# digit_8.net
KiCad netlist of a schematic drawn in EAGLE
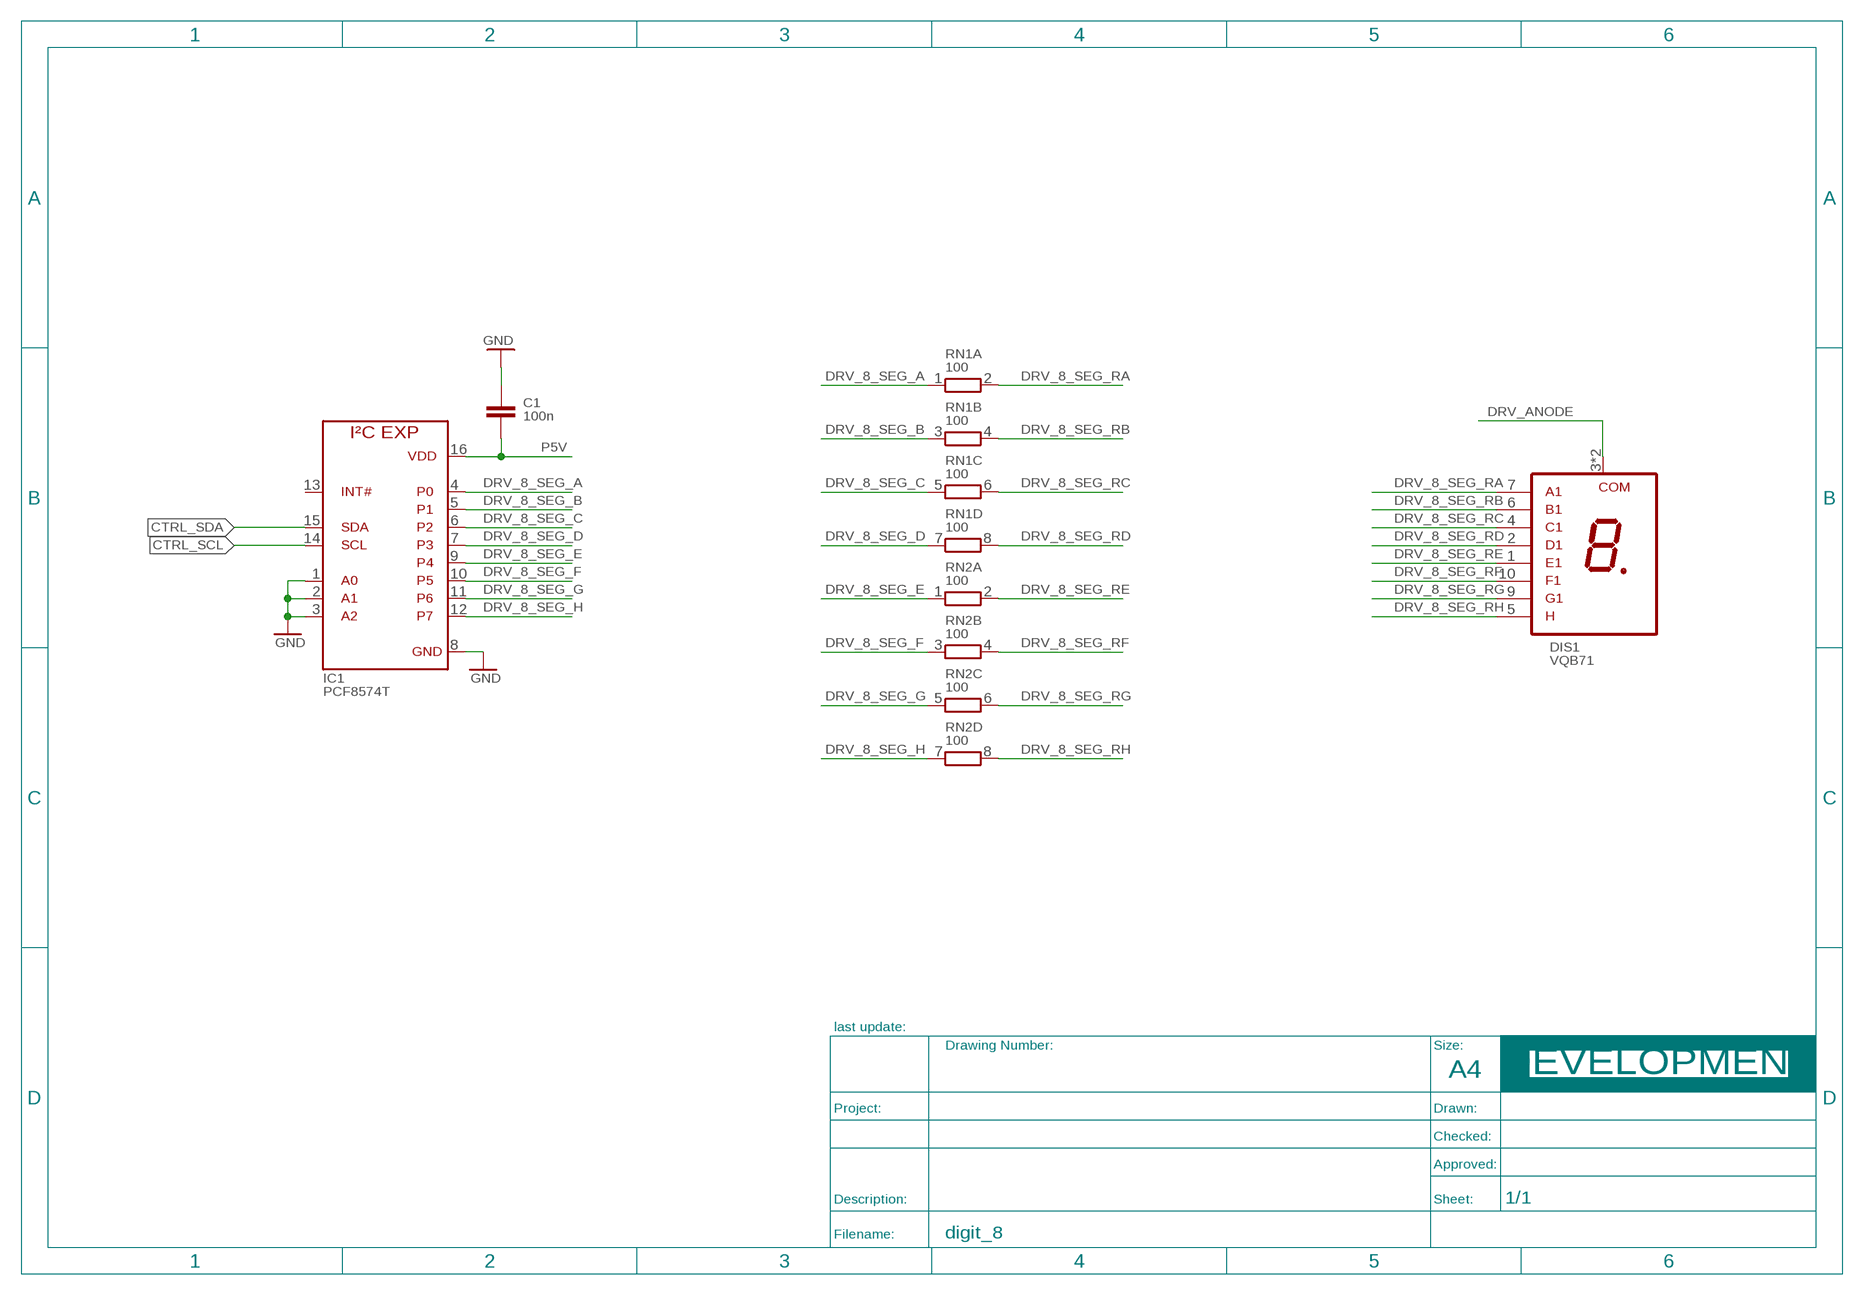
[diagram p0: schematic, sheet 1]

(export (version "E")
  (design (tool "Eeschema 10.0.6"))
  (components
    (comp (ref "C1")
      (value "100n")
      (footprint "eagle-import:S_0805")
      (fields (field (name "PART_CODE_BEL") "C_PAC_S_0805_VAL_100n"))
      (libsource (lib "eagle-import") (part "C_EU_S_0805"))
    )
    (comp (ref "DIS1")
      (value "VQB71")
      (footprint "eagle-import:T_VQB71")
      (libsource (lib "eagle-import") (part "VQB71"))
    )
    (comp (ref "IC1")
      (value "PCF8574T")
      (footprint "eagle-import:S_SOIC16")
      (libsource (lib "eagle-import") (part "PCF8574T"))
    )
    (comp (ref "RN1")
      (value "100")
      (footprint "eagle-import:T_SIL8")
      (fields (field (name "PART_CODE_BEL") "RN_PAC_T_SIL8_VAL_100"))
      (libsource (lib "eagle-import") (part "R_EU_ARRAY_4"))
    )
    (comp (ref "RN2")
      (value "100")
      (footprint "eagle-import:T_SIL8")
      (fields (field (name "PART_CODE_BEL") "RN_PAC_T_SIL8_VAL_100"))
      (libsource (lib "eagle-import") (part "R_EU_ARRAY_4"))
    )
  )
  (nets
    (net (code "1") (name "/DRV_8_SEG_A") (class "Default")
      (node (ref "IC1") (pin "4") (pinfunction "P0_4") (pintype "bidirectional"))
      (node (ref "RN1") (pin "1") (pinfunction "1_1") (pintype "passive"))
    )
    (net (code "2") (name "/DRV_8_SEG_B") (class "Default")
      (node (ref "IC1") (pin "5") (pinfunction "P1_5") (pintype "bidirectional"))
      (node (ref "RN1") (pin "3") (pinfunction "1_3") (pintype "passive"))
    )
    (net (code "3") (name "/DRV_8_SEG_C") (class "Default")
      (node (ref "IC1") (pin "6") (pinfunction "P2_6") (pintype "bidirectional"))
      (node (ref "RN1") (pin "5") (pinfunction "1_5") (pintype "passive"))
    )
    (net (code "4") (name "/DRV_8_SEG_D") (class "Default")
      (node (ref "IC1") (pin "7") (pinfunction "P3_7") (pintype "bidirectional"))
      (node (ref "RN1") (pin "7") (pinfunction "1_7") (pintype "passive"))
    )
    (net (code "5") (name "/DRV_8_SEG_E") (class "Default")
      (node (ref "IC1") (pin "9") (pinfunction "P4_9") (pintype "bidirectional"))
      (node (ref "RN2") (pin "1") (pinfunction "1_1") (pintype "passive"))
    )
    (net (code "6") (name "/DRV_8_SEG_F") (class "Default")
      (node (ref "IC1") (pin "10") (pinfunction "P5_10") (pintype "bidirectional"))
      (node (ref "RN2") (pin "3") (pinfunction "1_3") (pintype "passive"))
    )
    (net (code "7") (name "/DRV_8_SEG_G") (class "Default")
      (node (ref "IC1") (pin "11") (pinfunction "P6_11") (pintype "bidirectional"))
      (node (ref "RN2") (pin "5") (pinfunction "1_5") (pintype "passive"))
    )
    (net (code "8") (name "/DRV_8_SEG_H") (class "Default")
      (node (ref "IC1") (pin "12") (pinfunction "P7_12") (pintype "bidirectional"))
      (node (ref "RN2") (pin "7") (pinfunction "1_7") (pintype "passive"))
    )
    (net (code "9") (name "/DRV_8_SEG_RA") (class "Default")
      (node (ref "DIS1") (pin "7") (pinfunction "A1_7") (pintype "passive"))
      (node (ref "RN1") (pin "2") (pinfunction "2_2") (pintype "passive"))
    )
    (net (code "10") (name "/DRV_8_SEG_RB") (class "Default")
      (node (ref "DIS1") (pin "6") (pinfunction "B1_6") (pintype "passive"))
      (node (ref "RN1") (pin "4") (pinfunction "2_4") (pintype "passive"))
    )
    (net (code "11") (name "/DRV_8_SEG_RC") (class "Default")
      (node (ref "DIS1") (pin "4") (pinfunction "C1_4") (pintype "passive"))
      (node (ref "RN1") (pin "6") (pinfunction "2_6") (pintype "passive"))
    )
    (net (code "12") (name "/DRV_8_SEG_RD") (class "Default")
      (node (ref "DIS1") (pin "2") (pinfunction "D1_2") (pintype "passive"))
      (node (ref "RN1") (pin "8") (pinfunction "2_8") (pintype "passive"))
    )
    (net (code "13") (name "/DRV_8_SEG_RE") (class "Default")
      (node (ref "DIS1") (pin "1") (pinfunction "E1_1") (pintype "passive"))
      (node (ref "RN2") (pin "2") (pinfunction "2_2") (pintype "passive"))
    )
    (net (code "14") (name "/DRV_8_SEG_RF") (class "Default")
      (node (ref "DIS1") (pin "10") (pinfunction "F1_10") (pintype "passive"))
      (node (ref "RN2") (pin "4") (pinfunction "2_4") (pintype "passive"))
    )
    (net (code "15") (name "/DRV_8_SEG_RG") (class "Default")
      (node (ref "DIS1") (pin "9") (pinfunction "G1_9") (pintype "passive"))
      (node (ref "RN2") (pin "6") (pinfunction "2_6") (pintype "passive"))
    )
    (net (code "16") (name "/DRV_8_SEG_RH") (class "Default")
      (node (ref "DIS1") (pin "5") (pinfunction "DP1_5") (pintype "passive"))
      (node (ref "RN2") (pin "8") (pinfunction "2_8") (pintype "passive"))
    )
    (net (code "17") (name "/DRV_ANODE") (class "Default")
      (node (ref "DIS1") (pin "3") (pinfunction "COM1_3") (pintype "passive"))
      (node (ref "DIS1") (pin "8") (pinfunction "COM1_8") (pintype "passive"))
    )
    (net (code "18") (name "/P5V") (class "Default")
      (node (ref "C1") (pin "2") (pinfunction "2_2") (pintype "passive"))
      (node (ref "IC1") (pin "16") (pinfunction "VDD_16") (pintype "power_in"))
    )
    (net (code "19") (name "CTRL_SCL") (class "Default")
      (node (ref "IC1") (pin "14") (pinfunction "SCL_14") (pintype "input"))
    )
    (net (code "20") (name "CTRL_SDA") (class "Default")
      (node (ref "IC1") (pin "15") (pinfunction "SDA_15") (pintype "bidirectional"))
    )
    (net (code "21") (name "GND") (class "Default")
      (node (ref "C1") (pin "1") (pinfunction "1_1") (pintype "passive"))
      (node (ref "IC1") (pin "1") (pinfunction "A0_1") (pintype "input"))
      (node (ref "IC1") (pin "2") (pinfunction "A1_2") (pintype "input"))
      (node (ref "IC1") (pin "3") (pinfunction "A2_3") (pintype "input"))
      (node (ref "IC1") (pin "8") (pinfunction "GND_8") (pintype "power_in"))
    )
    (net (code "22") (name "unconnected-(IC1-~{INT}-Pad13)") (class "Default")
      (node (ref "IC1") (pin "13") (pinfunction "~{INT}_13") (pintype "output"))
    )
  )
)
